# Mother_Board.net
KiCad netlist of a schematic drawn in Altium Designer
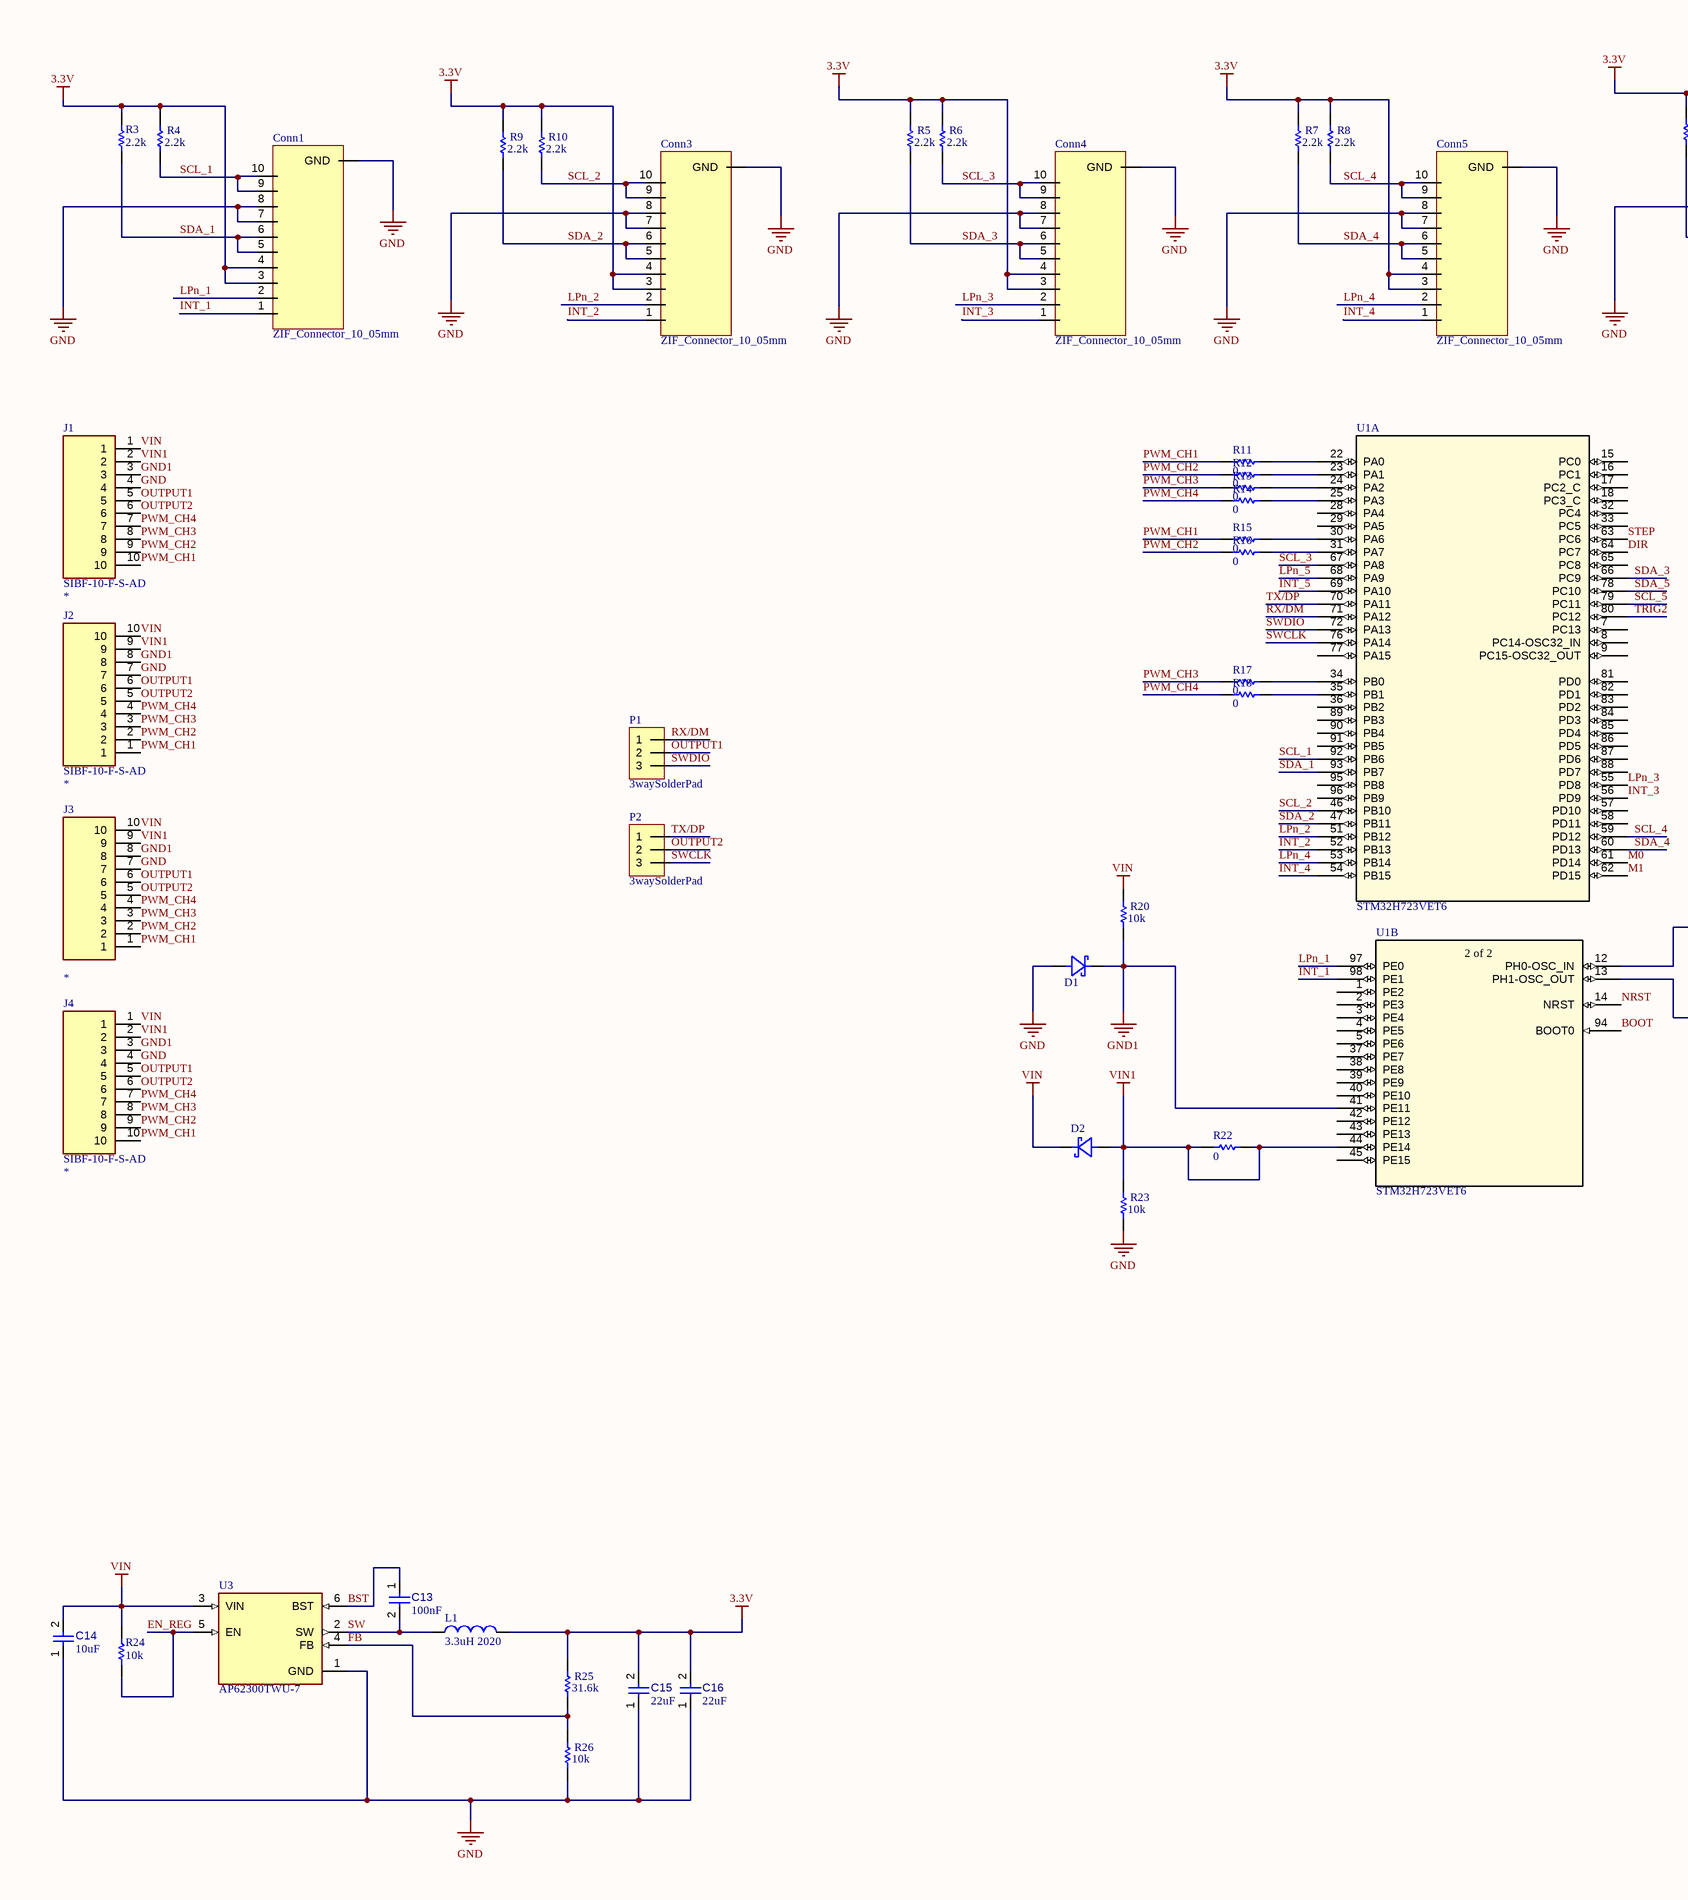
[diagram p0: Mother_Board.SchDoc, left]
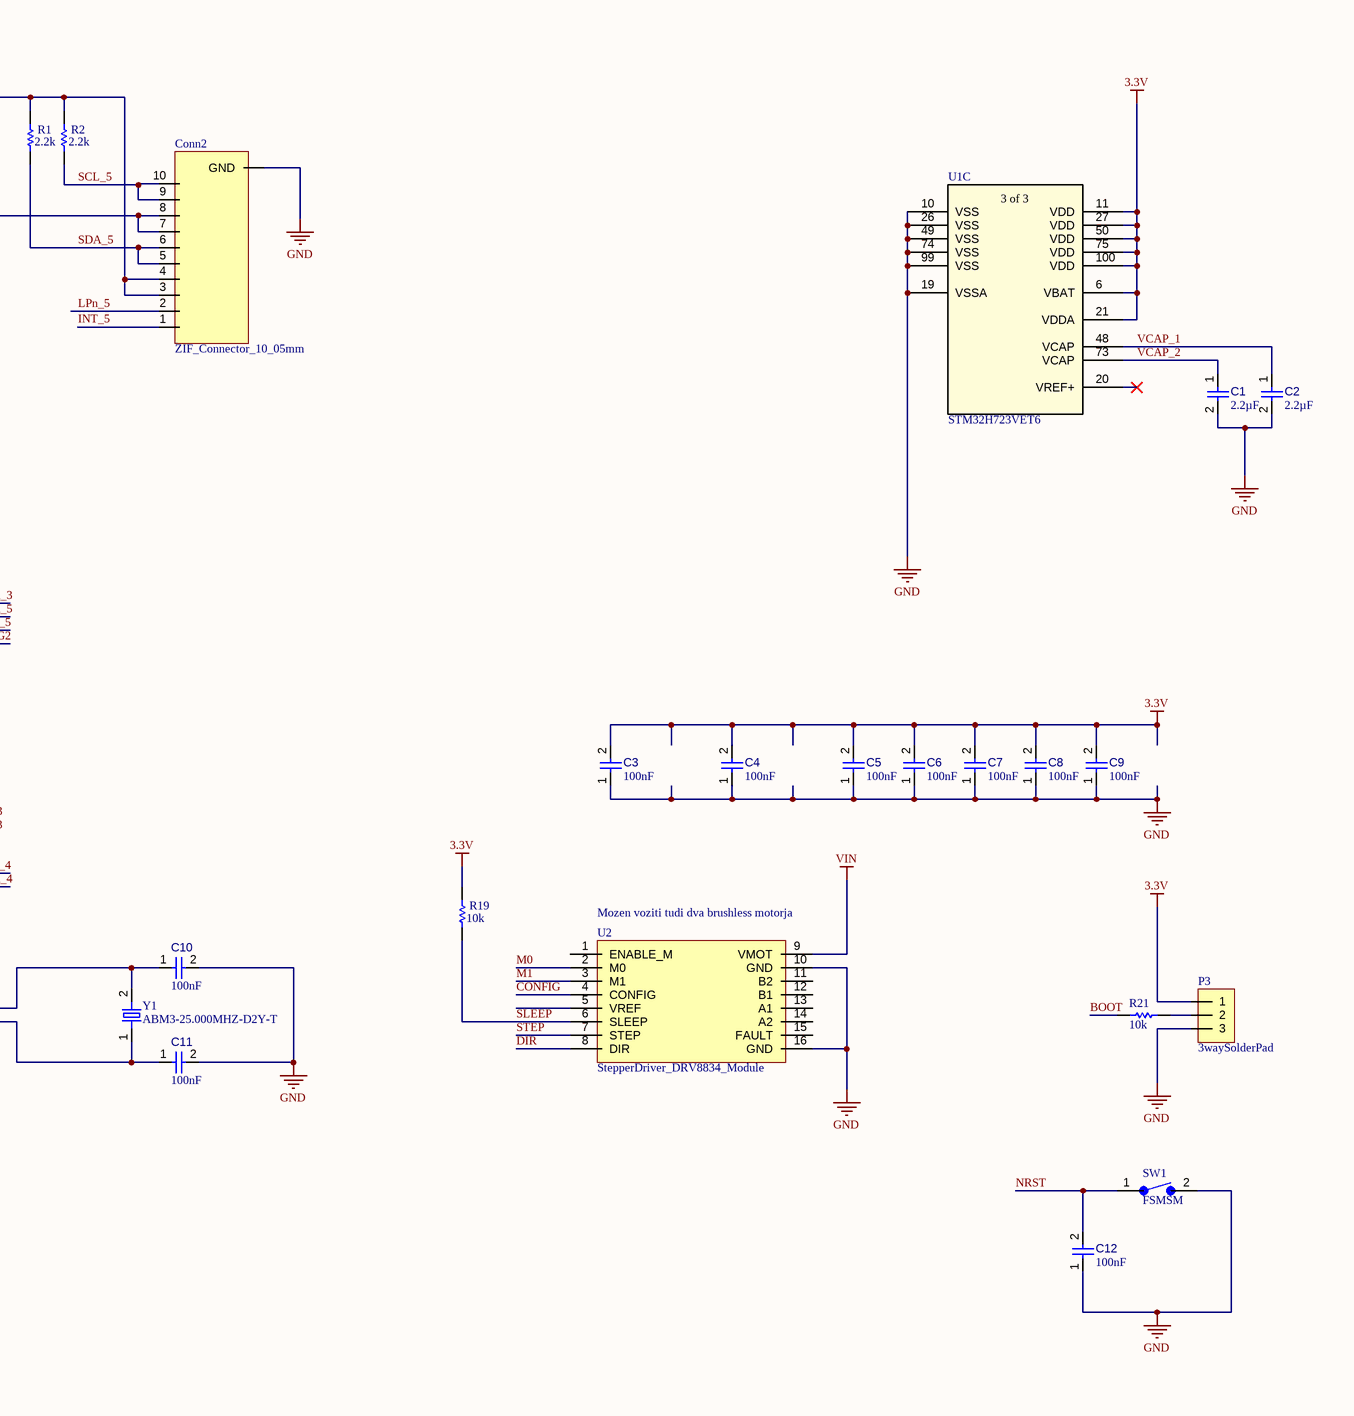
[diagram p1: Mother_Board.SchDoc, right]

(export (version "E")
  (design (tool "Eeschema 10.0.6"))
  (components
    (comp (ref "C1")
      (value "2.2µF")
      (footprint "CAPC0603(1608)100_L")
      (description "Chip Capacitor, 4.7µF +/-20%, 10V, 0603, Thickness 1 mm")
      (fields (field (name "TOLERANCE") "10%") (field (name "Comment") "Capacitor 4.7µF +/-20% 10V 0603"))
      (libsource (lib "Domen's Workpace") (part "CAP-NP-2"))
    )
    (comp (ref "C2")
      (value "2.2µF")
      (footprint "CAPC0603(1608)100_L")
      (description "Chip Capacitor, 4.7µF +/-20%, 10V, 0603, Thickness 1 mm")
      (fields (field (name "TOLERANCE") "10%") (field (name "Comment") "Capacitor 4.7µF +/-20% 10V 0603"))
      (libsource (lib "Domen's Workpace") (part "CAP-NP-2"))
    )
    (comp (ref "C3")
      (value "100nF")
      (footprint "CAPC0402(1005)60_L")
      (description "Chip Capacitor, 100nF +/-20%, 25V, 0402, Thickness 0.6 mm")
      (fields (field (name "TOLERANCE") "10%") (field (name "Comment") "Capacitor 100nF +/-20% 25V 0402"))
      (libsource (lib "Domen's Workpace") (part "CAP-NP-2"))
    )
    (comp (ref "C4")
      (value "100nF")
      (footprint "CAPC0402(1005)60_L")
      (description "Chip Capacitor, 100nF +/-20%, 25V, 0402, Thickness 0.6 mm")
      (fields (field (name "TOLERANCE") "10%") (field (name "Comment") "Capacitor 100nF +/-20% 25V 0402"))
      (libsource (lib "Domen's Workpace") (part "CAP-NP-2"))
    )
    (comp (ref "C5")
      (value "100nF")
      (footprint "CAPC0402(1005)60_L")
      (description "Chip Capacitor, 100nF +/-20%, 25V, 0402, Thickness 0.6 mm")
      (fields (field (name "TOLERANCE") "10%") (field (name "Comment") "Capacitor 100nF +/-20% 25V 0402"))
      (libsource (lib "Domen's Workpace") (part "CAP-NP-2"))
    )
    (comp (ref "C6")
      (value "100nF")
      (footprint "CAPC0402(1005)60_L")
      (description "Chip Capacitor, 100nF +/-20%, 25V, 0402, Thickness 0.6 mm")
      (fields (field (name "TOLERANCE") "10%") (field (name "Comment") "Capacitor 100nF +/-20% 25V 0402"))
      (libsource (lib "Domen's Workpace") (part "CAP-NP-2"))
    )
    (comp (ref "C7")
      (value "100nF")
      (footprint "CAPC0402(1005)60_L")
      (description "Chip Capacitor, 100nF +/-20%, 25V, 0402, Thickness 0.6 mm")
      (fields (field (name "TOLERANCE") "10%") (field (name "Comment") "Capacitor 100nF +/-20% 25V 0402"))
      (libsource (lib "Domen's Workpace") (part "CAP-NP-2"))
    )
    (comp (ref "C8")
      (value "100nF")
      (footprint "CAPC0402(1005)60_L")
      (description "Chip Capacitor, 100nF +/-20%, 25V, 0402, Thickness 0.6 mm")
      (fields (field (name "TOLERANCE") "10%") (field (name "Comment") "Capacitor 100nF +/-20% 25V 0402"))
      (libsource (lib "Domen's Workpace") (part "CAP-NP-2"))
    )
    (comp (ref "C9")
      (value "100nF")
      (footprint "CAPC0402(1005)60_L")
      (description "Chip Capacitor, 100nF +/-20%, 25V, 0402, Thickness 0.6 mm")
      (fields (field (name "TOLERANCE") "10%") (field (name "Comment") "Capacitor 100nF +/-20% 25V 0402"))
      (libsource (lib "Domen's Workpace") (part "CAP-NP-2"))
    )
    (comp (ref "C10")
      (value "100nF")
      (footprint "CAPC1608X90X40NL10T20")
      (description "Chip Capacitor, 100 nF, +/- 10%, 50 V, 0603 (1608 Metric)")
      (fields (field (name "TOLERANCE") "10%") (field (name "Comment") "Capacitor 100 nF +/-10% 50 V 0603"))
      (libsource (lib "Domen's Workpace") (part "CAP-NP-2"))
    )
    (comp (ref "C11")
      (value "100nF")
      (footprint "CAPC1608X90X40NL10T20")
      (description "Chip Capacitor, 100 nF, +/- 10%, 50 V, 0603 (1608 Metric)")
      (fields (field (name "TOLERANCE") "10%") (field (name "Comment") "Capacitor 100 nF +/-10% 50 V 0603"))
      (libsource (lib "Domen's Workpace") (part "CAP-NP-2"))
    )
    (comp (ref "C12")
      (value "100nF")
      (footprint "CAPC0402(1005)60_L")
      (description "Chip Capacitor, 100nF +/-20%, 25V, 0402, Thickness 0.6 mm")
      (fields (field (name "TOLERANCE") "10%") (field (name "Comment") "Capacitor 100nF +/-20% 25V 0402"))
      (libsource (lib "Domen's Workpace") (part "CAP-NP-2"))
    )
    (comp (ref "C13")
      (value "100nF")
      (footprint "CAPC1608X90X40NL10T20")
      (description "Chip Capacitor, 100 nF, +/- 10%, 50 V, 0603 (1608 Metric)")
      (fields (field (name "TOLERANCE") "10%") (field (name "Comment") "Capacitor 100 nF +/-10% 50 V 0603"))
      (libsource (lib "Domen's Workpace") (part "CAP-NP-2"))
    )
    (comp (ref "C14")
      (value "10uF")
      (footprint "CAPC3216X180X50NL20T25")
      (description "Chip Capacitor, 22 uF, +/- 10%, 16 V, 1206 (3216 Metric)")
      (fields (field (name "TOLERANCE") "10%") (field (name "Comment") "Capacitor 10 uF +/- 10% 16 V 1206"))
      (libsource (lib "Domen's Workpace") (part "CAP-NP-2"))
    )
    (comp (ref "C15")
      (value "22uF")
      (footprint "CAPC3216X180X50NL20T25")
      (description "Chip Capacitor, 22 uF, +/- 10%, 16 V, 1206 (3216 Metric)")
      (fields (field (name "TOLERANCE") "10%") (field (name "Comment") "Capacitor 10 uF +/- 10% 16 V 1206"))
      (libsource (lib "Domen's Workpace") (part "CAP-NP-2"))
    )
    (comp (ref "C16")
      (value "22uF")
      (footprint "CAPC3216X180X50NL20T25")
      (description "Chip Capacitor, 22 uF, +/- 10%, 16 V, 1206 (3216 Metric)")
      (fields (field (name "TOLERANCE") "10%") (field (name "Comment") "Capacitor 10 uF +/- 10% 16 V 1206"))
      (libsource (lib "Domen's Workpace") (part "CAP-NP-2"))
    )
    (comp (ref "Conn1")
      (value "ZIF_Connector_10_05mm")
      (footprint "ZIF_Connector_10_05mm")
      (libsource (lib "MainLib") (part "ZIF_Connector_10_05mm"))
    )
    (comp (ref "Conn2")
      (value "ZIF_Connector_10_05mm")
      (footprint "ZIF_Connector_10_05mm")
      (libsource (lib "MainLib") (part "ZIF_Connector_10_05mm"))
    )
    (comp (ref "Conn3")
      (value "ZIF_Connector_10_05mm")
      (footprint "ZIF_Connector_10_05mm")
      (libsource (lib "MainLib") (part "ZIF_Connector_10_05mm"))
    )
    (comp (ref "Conn4")
      (value "ZIF_Connector_10_05mm")
      (footprint "ZIF_Connector_10_05mm")
      (libsource (lib "MainLib") (part "ZIF_Connector_10_05mm"))
    )
    (comp (ref "Conn5")
      (value "ZIF_Connector_10_05mm")
      (footprint "ZIF_Connector_10_05mm")
      (libsource (lib "MainLib") (part "ZIF_Connector_10_05mm"))
    )
    (comp (ref "D1")
      (value "PMEG3030BEP,115")
      (footprint "PMEG3030BEP,115:CFP5_SOD128_NEX")
      (fields (field (name "MF") "{'manufacturer': u'Nexperia USA'}"))
      (libsource (lib "*") (part "PMEG3030BEP,115"))
    )
    (comp (ref "D2")
      (value "PMEG3030BEP,115")
      (footprint "PMEG3030BEP,115:CFP5_SOD128_NEX")
      (fields (field (name "MF") "{'manufacturer': u'Nexperia USA'}"))
      (libsource (lib "*") (part "PMEG3030BEP,115"))
    )
    (comp (ref "J1")
      (value "SIBF-10-F-S-AD")
      (footprint "SAMTEC_SIBF-10-F-S-AD")
      (fields (field (name "ALTIUM_VALUE") "*") (field (name "MF") "{'manufacturer': u'Samtec Inc.'}"))
      (libsource (lib "") (part "SIBF-10-F-S-AD_1"))
    )
    (comp (ref "J2")
      (value "SIBF-10-F-S-AD")
      (footprint "SAMTEC_SIBF-10-F-S-AD")
      (fields (field (name "ALTIUM_VALUE") "*") (field (name "MF") "{'manufacturer': u'Samtec Inc.'}"))
      (libsource (lib "SnapEDA_Library") (part "SIBF-10-F-S-AD"))
    )
    (comp (ref "J3")
      (value "~")
      (footprint "SAMTEC_SIBF-10-F-S-AD")
      (fields
        (field (name "ALTIUM_VALUE") "*")
        (field (name "MF") "{'manufacturer': u'Samtec Inc.'}")
        (field (name "MP") "SIBF-10-F-S-AD")
      )
      (libsource (lib "SnapEDA_Library") (part "SIBF-10-F-S-AD"))
    )
    (comp (ref "J4")
      (value "SIBF-10-F-S-AD")
      (footprint "SAMTEC_SIBF-10-F-S-AD")
      (fields (field (name "ALTIUM_VALUE") "*") (field (name "MF") "{'manufacturer': u'Samtec Inc.'}"))
      (libsource (lib "") (part "SIBF-10-F-S-AD_1"))
    )
    (comp (ref "L1")
      (value "3.3uH 2020")
      (footprint "IHLP2020CZER3R3M11:IHLP-2020CZ-11")
      (description "3.3ÂµH Shielded Molded Inductor 5.5A 40.4mOhm Max Nonstandard")
      (fields (field (name "MP") "IHLP2020CZER3R3M11") (field (name "MF") "{'manufacturer': u'Vishay Dale'}"))
      (libsource (lib "*") (part "IHLP2020CZER3R3M11"))
    )
    (comp (ref "P1")
      (value "3waySolderPad")
      (footprint "3waySolderPad")
      (libsource (lib "MainLib") (part "3waySolderPad"))
    )
    (comp (ref "P2")
      (value "3waySolderPad")
      (footprint "3waySolderPad")
      (libsource (lib "MainLib") (part "3waySolderPad"))
    )
    (comp (ref "P3")
      (value "3waySolderPad")
      (footprint "3waySolderPad")
      (libsource (lib "") (part "3waySolderPad_1"))
    )
    (comp (ref "R1")
      (value "2.2k")
      (footprint "RESC1608X55X25NL10T15")
      (description "Chip Resistor, 0 Ohm, 0.1 W, -55 to 155 degC, 0603 (1608 Metric)")
      (fields (field (name "POWER") "100mW") (field (name "TOLERANCE") "5%"))
      (libsource (lib "Domen's Workpace") (part "RES-2"))
    )
    (comp (ref "R2")
      (value "2.2k")
      (footprint "RESC1608X55X25NL10T15")
      (description "Chip Resistor, 0 Ohm, 0.1 W, -55 to 155 degC, 0603 (1608 Metric)")
      (fields (field (name "POWER") "100mW") (field (name "TOLERANCE") "5%"))
      (libsource (lib "Domen's Workpace") (part "RES-2"))
    )
    (comp (ref "R3")
      (value "2.2k")
      (footprint "RESC1608X55X25NL10T15")
      (description "Chip Resistor, 0 Ohm, 0.1 W, -55 to 155 degC, 0603 (1608 Metric)")
      (fields (field (name "POWER") "100mW") (field (name "TOLERANCE") "5%"))
      (libsource (lib "Domen's Workpace") (part "RES-2"))
    )
    (comp (ref "R4")
      (value "2.2k")
      (footprint "RESC1608X55X25NL10T15")
      (description "Chip Resistor, 0 Ohm, 0.1 W, -55 to 155 degC, 0603 (1608 Metric)")
      (fields (field (name "POWER") "100mW") (field (name "TOLERANCE") "5%"))
      (libsource (lib "Domen's Workpace") (part "RES-2"))
    )
    (comp (ref "R5")
      (value "2.2k")
      (footprint "RESC1608X55X25NL10T15")
      (description "Chip Resistor, 0 Ohm, 0.1 W, -55 to 155 degC, 0603 (1608 Metric)")
      (fields (field (name "POWER") "100mW") (field (name "TOLERANCE") "5%"))
      (libsource (lib "Domen's Workpace") (part "RES-2"))
    )
    (comp (ref "R6")
      (value "2.2k")
      (footprint "RESC1608X55X25NL10T15")
      (description "Chip Resistor, 0 Ohm, 0.1 W, -55 to 155 degC, 0603 (1608 Metric)")
      (fields (field (name "POWER") "100mW") (field (name "TOLERANCE") "5%"))
      (libsource (lib "Domen's Workpace") (part "RES-2"))
    )
    (comp (ref "R7")
      (value "2.2k")
      (footprint "RESC1608X55X25NL10T15")
      (description "Chip Resistor, 0 Ohm, 0.1 W, -55 to 155 degC, 0603 (1608 Metric)")
      (fields (field (name "POWER") "100mW") (field (name "TOLERANCE") "5%"))
      (libsource (lib "Domen's Workpace") (part "RES-2"))
    )
    (comp (ref "R8")
      (value "2.2k")
      (footprint "RESC1608X55X25NL10T15")
      (description "Chip Resistor, 0 Ohm, 0.1 W, -55 to 155 degC, 0603 (1608 Metric)")
      (fields (field (name "POWER") "100mW") (field (name "TOLERANCE") "5%"))
      (libsource (lib "Domen's Workpace") (part "RES-2"))
    )
    (comp (ref "R9")
      (value "2.2k")
      (footprint "RESC1608X55X25NL10T15")
      (description "Chip Resistor, 0 Ohm, 0.1 W, -55 to 155 degC, 0603 (1608 Metric)")
      (fields (field (name "POWER") "100mW") (field (name "TOLERANCE") "5%"))
      (libsource (lib "Domen's Workpace") (part "RES-2"))
    )
    (comp (ref "R10")
      (value "2.2k")
      (footprint "RESC1608X55X25NL10T15")
      (description "Chip Resistor, 0 Ohm, 0.1 W, -55 to 155 degC, 0603 (1608 Metric)")
      (fields (field (name "POWER") "100mW") (field (name "TOLERANCE") "5%"))
      (libsource (lib "Domen's Workpace") (part "RES-2"))
    )
    (comp (ref "R11")
      (value "0")
      (footprint "RESC1005X40X25ML05T05")
      (description "Chip Resistor, 0 Ohm, 0.1 W, -55 to 155 degC, 0402 (1005 Metric)")
      (fields (field (name "TOLERANCE") "5%") (field (name "POWER") "100mW"))
      (libsource (lib "Domen's Workpace") (part "RES-2"))
    )
    (comp (ref "R12")
      (value "0")
      (footprint "RESC1005X40X25ML05T05")
      (description "Chip Resistor, 0 Ohm, 0.1 W, -55 to 155 degC, 0402 (1005 Metric)")
      (fields (field (name "TOLERANCE") "5%") (field (name "POWER") "100mW"))
      (libsource (lib "Domen's Workpace") (part "RES-2"))
    )
    (comp (ref "R13")
      (value "0")
      (footprint "RESC1005X40X25ML05T05")
      (description "Chip Resistor, 0 Ohm, 0.1 W, -55 to 155 degC, 0402 (1005 Metric)")
      (fields (field (name "TOLERANCE") "5%") (field (name "POWER") "100mW"))
      (libsource (lib "Domen's Workpace") (part "RES-2"))
    )
    (comp (ref "R14")
      (value "0")
      (footprint "RESC1005X40X25ML05T05")
      (description "Chip Resistor, 0 Ohm, 0.1 W, -55 to 155 degC, 0402 (1005 Metric)")
      (fields (field (name "TOLERANCE") "5%") (field (name "POWER") "100mW"))
      (libsource (lib "Domen's Workpace") (part "RES-2"))
    )
    (comp (ref "R15")
      (value "0")
      (footprint "RESC1005X40X25ML05T05")
      (description "Chip Resistor, 0 Ohm, 0.1 W, -55 to 155 degC, 0402 (1005 Metric)")
      (fields (field (name "TOLERANCE") "5%") (field (name "POWER") "100mW"))
      (libsource (lib "Domen's Workpace") (part "RES-2"))
    )
    (comp (ref "R16")
      (value "0")
      (footprint "RESC1005X40X25ML05T05")
      (description "Chip Resistor, 0 Ohm, 0.1 W, -55 to 155 degC, 0402 (1005 Metric)")
      (fields (field (name "TOLERANCE") "5%") (field (name "POWER") "100mW"))
      (libsource (lib "Domen's Workpace") (part "RES-2"))
    )
    (comp (ref "R17")
      (value "0")
      (footprint "RESC1005X40X25ML05T05")
      (description "Chip Resistor, 0 Ohm, 0.1 W, -55 to 155 degC, 0402 (1005 Metric)")
      (fields (field (name "TOLERANCE") "5%") (field (name "POWER") "100mW"))
      (libsource (lib "Domen's Workpace") (part "RES-2"))
    )
    (comp (ref "R18")
      (value "0")
      (footprint "RESC1005X40X25ML05T05")
      (description "Chip Resistor, 0 Ohm, 0.1 W, -55 to 155 degC, 0402 (1005 Metric)")
      (fields (field (name "TOLERANCE") "5%") (field (name "POWER") "100mW"))
      (libsource (lib "Domen's Workpace") (part "RES-2"))
    )
    (comp (ref "R19")
      (value "10k")
      (footprint "RESC1608X55X25NL10T15")
      (description "Chip Resistor, 0 Ohm, 0.1 W, -55 to 155 degC, 0603 (1608 Metric)")
      (fields (field (name "POWER") "100mW") (field (name "TOLERANCE") "5%"))
      (libsource (lib "Domen's Workpace") (part "RES-2"))
    )
    (comp (ref "R20")
      (value "10k")
      (footprint "RESC1608X55X25NL10T15")
      (description "Chip Resistor, 0 Ohm, 0.1 W, -55 to 155 degC, 0603 (1608 Metric)")
      (fields (field (name "POWER") "100mW") (field (name "TOLERANCE") "5%"))
      (libsource (lib "Domen's Workpace") (part "RES-2"))
    )
    (comp (ref "R21")
      (value "10k")
      (footprint "RESC1608X55X25ML10T15")
      (description "Chip Resistor, 10 kOhm, 0.1 W, -55 to 155 degC, 0603 (1608 Metric)")
      (fields (field (name "POWER") "100mW") (field (name "TOLERANCE") "5%"))
      (libsource (lib "Domen's Workpace") (part "RES-2"))
    )
    (comp (ref "R22")
      (value "0")
      (footprint "RESC1005X40X25ML05T05")
      (description "Chip Resistor, 0 Ohm, 0.1 W, -55 to 155 degC, 0402 (1005 Metric)")
      (fields (field (name "TOLERANCE") "5%") (field (name "POWER") "100mW"))
      (libsource (lib "Domen's Workpace") (part "RES-2"))
    )
    (comp (ref "R23")
      (value "10k")
      (footprint "RESC1608X55X25NL10T15")
      (description "Chip Resistor, 0 Ohm, 0.1 W, -55 to 155 degC, 0603 (1608 Metric)")
      (fields (field (name "POWER") "100mW") (field (name "TOLERANCE") "5%"))
      (libsource (lib "Domen's Workpace") (part "RES-2"))
    )
    (comp (ref "R24")
      (value "10k")
      (footprint "RESC1608X55X25ML10T15")
      (description "Chip Resistor, 10 kOhm, 0.1 W, -55 to 155 degC, 0603 (1608 Metric)")
      (fields (field (name "POWER") "100mW") (field (name "TOLERANCE") "5%"))
      (libsource (lib "Domen's Workpace") (part "RES-2"))
    )
    (comp (ref "R25")
      (value "31.6k")
      (footprint "RESC1608X55X25NL10T15")
      (description "Chip Resistor, 0 Ohm, 0.1 W, -55 to 155 degC, 0603 (1608 Metric)")
      (fields (field (name "POWER") "100mW") (field (name "TOLERANCE") "5%"))
      (libsource (lib "Domen's Workpace") (part "RES-2"))
    )
    (comp (ref "R26")
      (value "10k")
      (footprint "RESC1608X55X25NL10T15")
      (description "Chip Resistor, 0 Ohm, 0.1 W, -55 to 155 degC, 0603 (1608 Metric)")
      (fields (field (name "POWER") "100mW") (field (name "TOLERANCE") "5%"))
      (libsource (lib "Domen's Workpace") (part "RES-2"))
    )
    (comp (ref "SW1")
      (value "FSMSM")
      (footprint "FSMSM:TE_FSMSM")
      (description "Switch Tactile OFF (ON) SPST Rectangular Button Gull Wing 0.05A 12VDC SMD Loose Piece")
      (fields (field (name "MF") "{'manufacturer': u'TE Connectivity'}"))
      (libsource (lib "*") (part "FSMSM"))
    )
    (comp (ref "U1")
      (value "STM32H723VET6")
      (footprint "LQFP100_STM")
      (description "No Description Available")
      (fields (field (name "COPYRIGHT") "Copyright (C) 2022 Ultra Librarian. All rights reserved."))
      (libsource (lib "MainLib") (part "STM32H723VET6"))
    )
    (comp (ref "U2")
      (value "StepperDriver_DRV8834_Module")
      (footprint "StepperDriver_DRV8834_Module")
      (libsource (lib "MainLib") (part "StepperDriver_DRV8834_Module"))
    )
    (comp (ref "U3")
      (value "AP62300TWU-7")
      (footprint "AP62300TWU-7:SOT95P280X100-6N")
      (fields (field (name "MF") "{'manufacturer': u'Diodes Incorporated'}"))
      (libsource (lib "*") (part "AP62300TWU-7"))
    )
    (comp (ref "Y1")
      (value "ABM3-25.000MHZ-D2Y-T")
      (footprint "XTAL500X320X130N")
      (description "Crystals 12MHz 18pF 30ppm -40C +85C")
      (fields (field (name "MF") "{'manufacturer': u'Abracon'}"))
      (libsource (lib "SnapEDA_Library") (part "ABM3-25.000MHZ-D2Y-T"))
    )
  )
  (nets
    (net (code "1") (name "/BOOT") (class "Default")
      (node (ref "R21") (pin "1") (pinfunction "1_1") (pintype "passive"))
      (node (ref "U1") (pin "94") (pinfunction "BOOT0_94") (pintype "input"))
    )
    (net (code "2") (name "/BST") (class "Default")
      (node (ref "C13") (pin "1") (pinfunction "1_1") (pintype "passive"))
      (node (ref "U3") (pin "6") (pinfunction "BST_6") (pintype "input"))
    )
    (net (code "3") (name "/CONFIG") (class "Default")
      (node (ref "U2") (pin "4") (pinfunction "CONFIG_4") (pintype "passive"))
    )
    (net (code "4") (name "/DIR") (class "Default")
      (node (ref "U1") (pin "64") (pinfunction "PC7_64") (pintype "bidirectional"))
      (node (ref "U2") (pin "8") (pinfunction "DIR_8") (pintype "passive"))
    )
    (net (code "5") (name "/EN_REG") (class "Default")
      (node (ref "R24") (pin "1") (pinfunction "1_1") (pintype "passive"))
      (node (ref "U3") (pin "5") (pinfunction "EN_5") (pintype "input"))
    )
    (net (code "6") (name "/FB") (class "Default")
      (node (ref "R25") (pin "2") (pinfunction "2_2") (pintype "passive"))
      (node (ref "R26") (pin "1") (pinfunction "1_1") (pintype "passive"))
      (node (ref "U3") (pin "4") (pinfunction "FB_4") (pintype "input"))
    )
    (net (code "7") (name "/INT_1") (class "Default")
      (node (ref "Conn1") (pin "1") (pinfunction "1_1") (pintype "passive"))
      (node (ref "U1") (pin "98") (pinfunction "PE1_98") (pintype "bidirectional"))
    )
    (net (code "8") (name "/INT_2") (class "Default")
      (node (ref "Conn3") (pin "1") (pinfunction "1_1") (pintype "passive"))
      (node (ref "U1") (pin "52") (pinfunction "PB13_52") (pintype "bidirectional"))
    )
    (net (code "9") (name "/INT_3") (class "Default")
      (node (ref "Conn4") (pin "1") (pinfunction "1_1") (pintype "passive"))
      (node (ref "U1") (pin "56") (pinfunction "PD9_56") (pintype "bidirectional"))
    )
    (net (code "10") (name "/INT_4") (class "Default")
      (node (ref "Conn5") (pin "1") (pinfunction "1_1") (pintype "passive"))
      (node (ref "U1") (pin "54") (pinfunction "PB15_54") (pintype "bidirectional"))
    )
    (net (code "11") (name "/INT_5") (class "Default")
      (node (ref "Conn2") (pin "1") (pinfunction "1_1") (pintype "passive"))
      (node (ref "U1") (pin "69") (pinfunction "PA10_69") (pintype "bidirectional"))
    )
    (net (code "12") (name "/LPn_1") (class "Default")
      (node (ref "Conn1") (pin "2") (pinfunction "2_2") (pintype "passive"))
      (node (ref "U1") (pin "97") (pinfunction "PE0_97") (pintype "bidirectional"))
    )
    (net (code "13") (name "/LPn_2") (class "Default")
      (node (ref "Conn3") (pin "2") (pinfunction "2_2") (pintype "passive"))
      (node (ref "U1") (pin "51") (pinfunction "PB12_51") (pintype "bidirectional"))
    )
    (net (code "14") (name "/LPn_3") (class "Default")
      (node (ref "Conn4") (pin "2") (pinfunction "2_2") (pintype "passive"))
      (node (ref "U1") (pin "55") (pinfunction "PD8_55") (pintype "bidirectional"))
    )
    (net (code "15") (name "/LPn_4") (class "Default")
      (node (ref "Conn5") (pin "2") (pinfunction "2_2") (pintype "passive"))
      (node (ref "U1") (pin "53") (pinfunction "PB14_53") (pintype "bidirectional"))
    )
    (net (code "16") (name "/LPn_5") (class "Default")
      (node (ref "Conn2") (pin "2") (pinfunction "2_2") (pintype "passive"))
      (node (ref "U1") (pin "68") (pinfunction "PA9_68") (pintype "bidirectional"))
    )
    (net (code "17") (name "/M0") (class "Default")
      (node (ref "U1") (pin "61") (pinfunction "PD14_61") (pintype "bidirectional"))
      (node (ref "U2") (pin "2") (pinfunction "M0_2") (pintype "passive"))
    )
    (net (code "18") (name "/M1") (class "Default")
      (node (ref "U1") (pin "62") (pinfunction "PD15_62") (pintype "bidirectional"))
      (node (ref "U2") (pin "3") (pinfunction "M1_3") (pintype "passive"))
    )
    (net (code "19") (name "/NRST") (class "Default")
      (node (ref "C12") (pin "2") (pinfunction "2_2") (pintype "passive"))
      (node (ref "SW1") (pin "1") (pinfunction "1_1") (pintype "passive"))
      (node (ref "U1") (pin "14") (pinfunction "NRST_14") (pintype "bidirectional"))
    )
    (net (code "20") (name "/OUTPUT1") (class "Default")
      (node (ref "J1") (pin "5") (pinfunction "5_5") (pintype "passive"))
      (node (ref "J2") (pin "6") (pinfunction "6_6") (pintype "passive"))
      (node (ref "J3") (pin "6") (pinfunction "6_6") (pintype "passive"))
      (node (ref "J4") (pin "5") (pinfunction "5_5") (pintype "passive"))
      (node (ref "P1") (pin "2") (pinfunction "2_2") (pintype "passive"))
    )
    (net (code "21") (name "/OUTPUT2") (class "Default")
      (node (ref "J1") (pin "6") (pinfunction "6_6") (pintype "passive"))
      (node (ref "J2") (pin "5") (pinfunction "5_5") (pintype "passive"))
      (node (ref "J3") (pin "5") (pinfunction "5_5") (pintype "passive"))
      (node (ref "J4") (pin "6") (pinfunction "6_6") (pintype "passive"))
      (node (ref "P2") (pin "2") (pinfunction "2_2") (pintype "passive"))
    )
    (net (code "22") (name "/PWM_CH1") (class "Default")
      (node (ref "J1") (pin "10") (pinfunction "10_10") (pintype "passive"))
      (node (ref "J2") (pin "1") (pinfunction "1_1") (pintype "passive"))
      (node (ref "J3") (pin "1") (pinfunction "1_1") (pintype "passive"))
      (node (ref "J4") (pin "10") (pinfunction "10_10") (pintype "passive"))
      (node (ref "R11") (pin "1") (pinfunction "1_1") (pintype "passive"))
      (node (ref "R15") (pin "1") (pinfunction "1_1") (pintype "passive"))
    )
    (net (code "23") (name "/PWM_CH2") (class "Default")
      (node (ref "J1") (pin "9") (pinfunction "9_9") (pintype "passive"))
      (node (ref "J2") (pin "2") (pinfunction "2_2") (pintype "passive"))
      (node (ref "J3") (pin "2") (pinfunction "2_2") (pintype "passive"))
      (node (ref "J4") (pin "9") (pinfunction "9_9") (pintype "passive"))
      (node (ref "R12") (pin "1") (pinfunction "1_1") (pintype "passive"))
      (node (ref "R16") (pin "1") (pinfunction "1_1") (pintype "passive"))
    )
    (net (code "24") (name "/PWM_CH3") (class "Default")
      (node (ref "J1") (pin "8") (pinfunction "8_8") (pintype "passive"))
      (node (ref "J2") (pin "3") (pinfunction "3_3") (pintype "passive"))
      (node (ref "J3") (pin "3") (pinfunction "3_3") (pintype "passive"))
      (node (ref "J4") (pin "8") (pinfunction "8_8") (pintype "passive"))
      (node (ref "R13") (pin "1") (pinfunction "1_1") (pintype "passive"))
      (node (ref "R17") (pin "1") (pinfunction "1_1") (pintype "passive"))
    )
    (net (code "25") (name "/PWM_CH4") (class "Default")
      (node (ref "J1") (pin "7") (pinfunction "7_7") (pintype "passive"))
      (node (ref "J2") (pin "4") (pinfunction "4_4") (pintype "passive"))
      (node (ref "J3") (pin "4") (pinfunction "4_4") (pintype "passive"))
      (node (ref "J4") (pin "7") (pinfunction "7_7") (pintype "passive"))
      (node (ref "R14") (pin "1") (pinfunction "1_1") (pintype "passive"))
      (node (ref "R18") (pin "1") (pinfunction "1_1") (pintype "passive"))
    )
    (net (code "26") (name "/RX{slash}DM") (class "Default")
      (node (ref "P1") (pin "1") (pinfunction "1_1") (pintype "passive"))
      (node (ref "U1") (pin "71") (pinfunction "PA12_71") (pintype "bidirectional"))
    )
    (net (code "27") (name "/SCL_1") (class "Default")
      (node (ref "Conn1") (pin "10") (pinfunction "10_10") (pintype "passive"))
      (node (ref "Conn1") (pin "9") (pinfunction "9_9") (pintype "passive"))
      (node (ref "R4") (pin "2") (pinfunction "2_2") (pintype "passive"))
      (node (ref "U1") (pin "92") (pinfunction "PB6_92") (pintype "bidirectional"))
    )
    (net (code "28") (name "/SCL_2") (class "Default")
      (node (ref "Conn3") (pin "10") (pinfunction "10_10") (pintype "passive"))
      (node (ref "Conn3") (pin "9") (pinfunction "9_9") (pintype "passive"))
      (node (ref "R10") (pin "2") (pinfunction "2_2") (pintype "passive"))
      (node (ref "U1") (pin "46") (pinfunction "PB10_46") (pintype "bidirectional"))
    )
    (net (code "29") (name "/SCL_3") (class "Default")
      (node (ref "Conn4") (pin "10") (pinfunction "10_10") (pintype "passive"))
      (node (ref "Conn4") (pin "9") (pinfunction "9_9") (pintype "passive"))
      (node (ref "R6") (pin "2") (pinfunction "2_2") (pintype "passive"))
      (node (ref "U1") (pin "67") (pinfunction "PA8_67") (pintype "bidirectional"))
    )
    (net (code "30") (name "/SCL_4") (class "Default")
      (node (ref "Conn5") (pin "10") (pinfunction "10_10") (pintype "passive"))
      (node (ref "Conn5") (pin "9") (pinfunction "9_9") (pintype "passive"))
      (node (ref "R8") (pin "2") (pinfunction "2_2") (pintype "passive"))
      (node (ref "U1") (pin "59") (pinfunction "PD12_59") (pintype "bidirectional"))
    )
    (net (code "31") (name "/SCL_5") (class "Default")
      (node (ref "Conn2") (pin "10") (pinfunction "10_10") (pintype "passive"))
      (node (ref "Conn2") (pin "9") (pinfunction "9_9") (pintype "passive"))
      (node (ref "R2") (pin "2") (pinfunction "2_2") (pintype "passive"))
      (node (ref "U1") (pin "79") (pinfunction "PC11_79") (pintype "bidirectional"))
    )
    (net (code "32") (name "/SDA_1") (class "Default")
      (node (ref "Conn1") (pin "5") (pinfunction "5_5") (pintype "passive"))
      (node (ref "Conn1") (pin "6") (pinfunction "6_6") (pintype "passive"))
      (node (ref "R3") (pin "2") (pinfunction "2_2") (pintype "passive"))
      (node (ref "U1") (pin "93") (pinfunction "PB7_93") (pintype "bidirectional"))
    )
    (net (code "33") (name "/SDA_2") (class "Default")
      (node (ref "Conn3") (pin "5") (pinfunction "5_5") (pintype "passive"))
      (node (ref "Conn3") (pin "6") (pinfunction "6_6") (pintype "passive"))
      (node (ref "R9") (pin "2") (pinfunction "2_2") (pintype "passive"))
      (node (ref "U1") (pin "47") (pinfunction "PB11_47") (pintype "bidirectional"))
    )
    (net (code "34") (name "/SDA_3") (class "Default")
      (node (ref "Conn4") (pin "5") (pinfunction "5_5") (pintype "passive"))
      (node (ref "Conn4") (pin "6") (pinfunction "6_6") (pintype "passive"))
      (node (ref "R5") (pin "2") (pinfunction "2_2") (pintype "passive"))
      (node (ref "U1") (pin "66") (pinfunction "PC9_66") (pintype "bidirectional"))
    )
    (net (code "35") (name "/SDA_4") (class "Default")
      (node (ref "Conn5") (pin "5") (pinfunction "5_5") (pintype "passive"))
      (node (ref "Conn5") (pin "6") (pinfunction "6_6") (pintype "passive"))
      (node (ref "R7") (pin "2") (pinfunction "2_2") (pintype "passive"))
      (node (ref "U1") (pin "60") (pinfunction "PD13_60") (pintype "bidirectional"))
    )
    (net (code "36") (name "/SDA_5") (class "Default")
      (node (ref "Conn2") (pin "5") (pinfunction "5_5") (pintype "passive"))
      (node (ref "Conn2") (pin "6") (pinfunction "6_6") (pintype "passive"))
      (node (ref "R1") (pin "2") (pinfunction "2_2") (pintype "passive"))
      (node (ref "U1") (pin "78") (pinfunction "PC10_78") (pintype "bidirectional"))
    )
    (net (code "37") (name "/SLEEP") (class "Default")
      (node (ref "R19") (pin "2") (pinfunction "2_2") (pintype "passive"))
      (node (ref "U2") (pin "6") (pinfunction "SLEEP_6") (pintype "passive"))
    )
    (net (code "38") (name "/STEP") (class "Default")
      (node (ref "U1") (pin "63") (pinfunction "PC6_63") (pintype "bidirectional"))
      (node (ref "U2") (pin "7") (pinfunction "STEP_7") (pintype "passive"))
    )
    (net (code "39") (name "/SW") (class "Default")
      (node (ref "C13") (pin "2") (pinfunction "2_2") (pintype "passive"))
      (node (ref "L1") (pin "P$1") (pinfunction "P$1_P$1") (pintype "bidirectional"))
      (node (ref "U3") (pin "2") (pinfunction "SW_2") (pintype "output"))
    )
    (net (code "40") (name "/SWCLK") (class "Default")
      (node (ref "P2") (pin "3") (pinfunction "3_3") (pintype "passive"))
      (node (ref "U1") (pin "76") (pinfunction "PA14_76") (pintype "bidirectional"))
    )
    (net (code "41") (name "/SWDIO") (class "Default")
      (node (ref "P1") (pin "3") (pinfunction "3_3") (pintype "passive"))
      (node (ref "U1") (pin "72") (pinfunction "PA13_72") (pintype "bidirectional"))
    )
    (net (code "42") (name "/TRIG2") (class "Default")
      (node (ref "U1") (pin "80") (pinfunction "PC12_80") (pintype "bidirectional"))
    )
    (net (code "43") (name "/TX{slash}DP") (class "Default")
      (node (ref "P2") (pin "1") (pinfunction "1_1") (pintype "passive"))
      (node (ref "U1") (pin "70") (pinfunction "PA11_70") (pintype "bidirectional"))
    )
    (net (code "44") (name "/VCAP_1") (class "Default")
      (node (ref "C2") (pin "1") (pinfunction "1_1") (pintype "passive"))
      (node (ref "U1") (pin "48") (pinfunction "VCAP_48") (pintype "power_in"))
    )
    (net (code "45") (name "/VCAP_2") (class "Default")
      (node (ref "C1") (pin "1") (pinfunction "1_1") (pintype "passive"))
      (node (ref "U1") (pin "73") (pinfunction "VCAP_73") (pintype "power_in"))
    )
    (net (code "46") (name "3.3V") (class "Default")
      (node (ref "C15") (pin "2") (pinfunction "2_2") (pintype "passive"))
      (node (ref "C16") (pin "2") (pinfunction "2_2") (pintype "passive"))
      (node (ref "C3") (pin "2") (pinfunction "2_2") (pintype "passive"))
      (node (ref "C4") (pin "2") (pinfunction "2_2") (pintype "passive"))
      (node (ref "C5") (pin "2") (pinfunction "2_2") (pintype "passive"))
      (node (ref "C6") (pin "2") (pinfunction "2_2") (pintype "passive"))
      (node (ref "C7") (pin "2") (pinfunction "2_2") (pintype "passive"))
      (node (ref "C8") (pin "2") (pinfunction "2_2") (pintype "passive"))
      (node (ref "C9") (pin "2") (pinfunction "2_2") (pintype "passive"))
      (node (ref "Conn1") (pin "3") (pinfunction "3_3") (pintype "passive"))
      (node (ref "Conn1") (pin "4") (pinfunction "4_4") (pintype "passive"))
      (node (ref "Conn2") (pin "3") (pinfunction "3_3") (pintype "passive"))
      (node (ref "Conn2") (pin "4") (pinfunction "4_4") (pintype "passive"))
      (node (ref "Conn3") (pin "3") (pinfunction "3_3") (pintype "passive"))
      (node (ref "Conn3") (pin "4") (pinfunction "4_4") (pintype "passive"))
      (node (ref "Conn4") (pin "3") (pinfunction "3_3") (pintype "passive"))
      (node (ref "Conn4") (pin "4") (pinfunction "4_4") (pintype "passive"))
      (node (ref "Conn5") (pin "3") (pinfunction "3_3") (pintype "passive"))
      (node (ref "Conn5") (pin "4") (pinfunction "4_4") (pintype "passive"))
      (node (ref "L1") (pin "P$2") (pinfunction "P$2_P$2") (pintype "bidirectional"))
      (node (ref "P3") (pin "1") (pinfunction "1_1") (pintype "passive"))
      (node (ref "R1") (pin "1") (pinfunction "1_1") (pintype "passive"))
      (node (ref "R10") (pin "1") (pinfunction "1_1") (pintype "passive"))
      (node (ref "R19") (pin "1") (pinfunction "1_1") (pintype "passive"))
      (node (ref "R2") (pin "1") (pinfunction "1_1") (pintype "passive"))
      (node (ref "R25") (pin "1") (pinfunction "1_1") (pintype "passive"))
      (node (ref "R3") (pin "1") (pinfunction "1_1") (pintype "passive"))
      (node (ref "R4") (pin "1") (pinfunction "1_1") (pintype "passive"))
      (node (ref "R5") (pin "1") (pinfunction "1_1") (pintype "passive"))
      (node (ref "R6") (pin "1") (pinfunction "1_1") (pintype "passive"))
      (node (ref "R7") (pin "1") (pinfunction "1_1") (pintype "passive"))
      (node (ref "R8") (pin "1") (pinfunction "1_1") (pintype "passive"))
      (node (ref "R9") (pin "1") (pinfunction "1_1") (pintype "passive"))
      (node (ref "U1") (pin "100") (pinfunction "VDD_100") (pintype "power_in"))
      (node (ref "U1") (pin "11") (pinfunction "VDD_11") (pintype "power_in"))
      (node (ref "U1") (pin "21") (pinfunction "VDDA_21") (pintype "power_in"))
      (node (ref "U1") (pin "27") (pinfunction "VDD_27") (pintype "power_in"))
      (node (ref "U1") (pin "50") (pinfunction "VDD_50") (pintype "power_in"))
      (node (ref "U1") (pin "6") (pinfunction "VBAT_6") (pintype "power_in"))
      (node (ref "U1") (pin "75") (pinfunction "VDD_75") (pintype "power_in"))
    )
    (net (code "47") (name "GND") (class "Default")
      (node (ref "C1") (pin "2") (pinfunction "2_2") (pintype "passive"))
      (node (ref "C10") (pin "2") (pinfunction "2_2") (pintype "passive"))
      (node (ref "C11") (pin "2") (pinfunction "2_2") (pintype "passive"))
      (node (ref "C12") (pin "1") (pinfunction "1_1") (pintype "passive"))
      (node (ref "C14") (pin "1") (pinfunction "1_1") (pintype "passive"))
      (node (ref "C15") (pin "1") (pinfunction "1_1") (pintype "passive"))
      (node (ref "C16") (pin "1") (pinfunction "1_1") (pintype "passive"))
      (node (ref "C2") (pin "2") (pinfunction "2_2") (pintype "passive"))
      (node (ref "C3") (pin "1") (pinfunction "1_1") (pintype "passive"))
      (node (ref "C4") (pin "1") (pinfunction "1_1") (pintype "passive"))
      (node (ref "C5") (pin "1") (pinfunction "1_1") (pintype "passive"))
      (node (ref "C6") (pin "1") (pinfunction "1_1") (pintype "passive"))
      (node (ref "C7") (pin "1") (pinfunction "1_1") (pintype "passive"))
      (node (ref "C8") (pin "1") (pinfunction "1_1") (pintype "passive"))
      (node (ref "C9") (pin "1") (pinfunction "1_1") (pintype "passive"))
      (node (ref "Conn1") (pin "7") (pinfunction "7_7") (pintype "passive"))
      (node (ref "Conn1") (pin "8") (pinfunction "8_8") (pintype "passive"))
      (node (ref "Conn1") (pin "GND") (pinfunction "GND_GND") (pintype "passive"))
      (node (ref "Conn2") (pin "7") (pinfunction "7_7") (pintype "passive"))
      (node (ref "Conn2") (pin "8") (pinfunction "8_8") (pintype "passive"))
      (node (ref "Conn2") (pin "GND") (pinfunction "GND_GND") (pintype "passive"))
      (node (ref "Conn3") (pin "7") (pinfunction "7_7") (pintype "passive"))
      (node (ref "Conn3") (pin "8") (pinfunction "8_8") (pintype "passive"))
      (node (ref "Conn3") (pin "GND") (pinfunction "GND_GND") (pintype "passive"))
      (node (ref "Conn4") (pin "7") (pinfunction "7_7") (pintype "passive"))
      (node (ref "Conn4") (pin "8") (pinfunction "8_8") (pintype "passive"))
      (node (ref "Conn4") (pin "GND") (pinfunction "GND_GND") (pintype "passive"))
      (node (ref "Conn5") (pin "7") (pinfunction "7_7") (pintype "passive"))
      (node (ref "Conn5") (pin "8") (pinfunction "8_8") (pintype "passive"))
      (node (ref "Conn5") (pin "GND") (pinfunction "GND_GND") (pintype "passive"))
      (node (ref "D1") (pin "2") (pinfunction "12_2") (pintype "passive"))
      (node (ref "J1") (pin "4") (pinfunction "4_4") (pintype "passive"))
      (node (ref "J2") (pin "7") (pinfunction "7_7") (pintype "passive"))
      (node (ref "J3") (pin "7") (pinfunction "7_7") (pintype "passive"))
      (node (ref "J4") (pin "4") (pinfunction "4_4") (pintype "passive"))
      (node (ref "P3") (pin "3") (pinfunction "3_3") (pintype "passive"))
      (node (ref "R23") (pin "2") (pinfunction "2_2") (pintype "passive"))
      (node (ref "R26") (pin "2") (pinfunction "2_2") (pintype "passive"))
      (node (ref "SW1") (pin "2") (pinfunction "2_2") (pintype "passive"))
      (node (ref "U1") (pin "10") (pinfunction "VSS_10") (pintype "power_in"))
      (node (ref "U1") (pin "19") (pinfunction "VSSA_19") (pintype "power_in"))
      (node (ref "U1") (pin "26") (pinfunction "VSS_26") (pintype "power_in"))
      (node (ref "U1") (pin "49") (pinfunction "VSS_49") (pintype "power_in"))
      (node (ref "U1") (pin "74") (pinfunction "VSS_74") (pintype "power_in"))
      (node (ref "U1") (pin "99") (pinfunction "VSS_99") (pintype "power_in"))
      (node (ref "U2") (pin "10") (pinfunction "GND_10") (pintype "passive"))
      (node (ref "U2") (pin "16") (pinfunction "GND_16") (pintype "passive"))
      (node (ref "U3") (pin "1") (pinfunction "GND_1") (pintype "power_in"))
    )
    (net (code "48") (name "GND1") (class "Default")
      (node (ref "D1") (pin "1") (pinfunction "11_1") (pintype "passive"))
      (node (ref "J1") (pin "3") (pinfunction "3_3") (pintype "passive"))
      (node (ref "J2") (pin "8") (pinfunction "8_8") (pintype "passive"))
      (node (ref "J3") (pin "8") (pinfunction "8_8") (pintype "passive"))
      (node (ref "J4") (pin "3") (pinfunction "3_3") (pintype "passive"))
      (node (ref "R20") (pin "2") (pinfunction "2_2") (pintype "passive"))
      (node (ref "U1") (pin "41") (pinfunction "PE11_41") (pintype "bidirectional"))
    )
    (net (code "49") (name "Net-(P3-Pad2)") (class "Default")
      (node (ref "P3") (pin "2") (pinfunction "2_2") (pintype "passive"))
      (node (ref "R21") (pin "2") (pinfunction "2_2") (pintype "passive"))
    )
    (net (code "50") (name "Net-(U1A-PA0)") (class "Default")
      (node (ref "R11") (pin "2") (pinfunction "2_2") (pintype "passive"))
      (node (ref "U1") (pin "22") (pinfunction "PA0_22") (pintype "bidirectional"))
    )
    (net (code "51") (name "Net-(U1A-PA1)") (class "Default")
      (node (ref "R12") (pin "2") (pinfunction "2_2") (pintype "passive"))
      (node (ref "U1") (pin "23") (pinfunction "PA1_23") (pintype "bidirectional"))
    )
    (net (code "52") (name "Net-(U1A-PA2)") (class "Default")
      (node (ref "R13") (pin "2") (pinfunction "2_2") (pintype "passive"))
      (node (ref "U1") (pin "24") (pinfunction "PA2_24") (pintype "bidirectional"))
    )
    (net (code "53") (name "Net-(U1A-PA3)") (class "Default")
      (node (ref "R14") (pin "2") (pinfunction "2_2") (pintype "passive"))
      (node (ref "U1") (pin "25") (pinfunction "PA3_25") (pintype "bidirectional"))
    )
    (net (code "54") (name "Net-(U1A-PA6)") (class "Default")
      (node (ref "R15") (pin "2") (pinfunction "2_2") (pintype "passive"))
      (node (ref "U1") (pin "30") (pinfunction "PA6_30") (pintype "bidirectional"))
    )
    (net (code "55") (name "Net-(U1A-PA7)") (class "Default")
      (node (ref "R16") (pin "2") (pinfunction "2_2") (pintype "passive"))
      (node (ref "U1") (pin "31") (pinfunction "PA7_31") (pintype "bidirectional"))
    )
    (net (code "56") (name "Net-(U1A-PB0)") (class "Default")
      (node (ref "R17") (pin "2") (pinfunction "2_2") (pintype "passive"))
      (node (ref "U1") (pin "34") (pinfunction "PB0_34") (pintype "bidirectional"))
    )
    (net (code "57") (name "Net-(U1A-PB1)") (class "Default")
      (node (ref "R18") (pin "2") (pinfunction "2_2") (pintype "passive"))
      (node (ref "U1") (pin "35") (pinfunction "PB1_35") (pintype "bidirectional"))
    )
    (net (code "58") (name "Net-(U1B-PH0-OSC_IN)") (class "Default")
      (node (ref "C10") (pin "1") (pinfunction "1_1") (pintype "passive"))
      (node (ref "U1") (pin "12") (pinfunction "PH0-OSC_IN_12") (pintype "bidirectional"))
      (node (ref "Y1") (pin "2") (pinfunction "2_2") (pintype "passive"))
    )
    (net (code "59") (name "Net-(U1B-PH1-OSC_OUT)") (class "Default")
      (node (ref "C11") (pin "1") (pinfunction "1_1") (pintype "passive"))
      (node (ref "U1") (pin "13") (pinfunction "PH1-OSC_OUT_13") (pintype "bidirectional"))
      (node (ref "Y1") (pin "1") (pinfunction "1_1") (pintype "passive"))
    )
    (net (code "60") (name "VIN") (class "Default")
      (node (ref "C14") (pin "2") (pinfunction "2_2") (pintype "passive"))
      (node (ref "D2") (pin "1") (pinfunction "11_1") (pintype "passive"))
      (node (ref "J1") (pin "1") (pinfunction "1_1") (pintype "passive"))
      (node (ref "J2") (pin "10") (pinfunction "10_10") (pintype "passive"))
      (node (ref "J3") (pin "10") (pinfunction "10_10") (pintype "passive"))
      (node (ref "J4") (pin "1") (pinfunction "1_1") (pintype "passive"))
      (node (ref "R20") (pin "1") (pinfunction "1_1") (pintype "passive"))
      (node (ref "R24") (pin "2") (pinfunction "2_2") (pintype "passive"))
      (node (ref "U2") (pin "9") (pinfunction "VMOT_9") (pintype "passive"))
      (node (ref "U3") (pin "3") (pinfunction "VIN_3") (pintype "input"))
    )
    (net (code "61") (name "VIN1") (class "Default")
      (node (ref "D2") (pin "2") (pinfunction "12_2") (pintype "passive"))
      (node (ref "J1") (pin "2") (pinfunction "2_2") (pintype "passive"))
      (node (ref "J2") (pin "9") (pinfunction "9_9") (pintype "passive"))
      (node (ref "J3") (pin "9") (pinfunction "9_9") (pintype "passive"))
      (node (ref "J4") (pin "2") (pinfunction "2_2") (pintype "passive"))
      (node (ref "R22") (pin "1") (pinfunction "1_1") (pintype "passive"))
      (node (ref "R22") (pin "2") (pinfunction "2_2") (pintype "passive"))
      (node (ref "R23") (pin "1") (pinfunction "1_1") (pintype "passive"))
      (node (ref "U1") (pin "44") (pinfunction "PE14_44") (pintype "bidirectional"))
    )
    (net (code "62") (name "unconnected-(U1A-PA4-Pad28)") (class "Default")
      (node (ref "U1") (pin "28") (pinfunction "PA4_28") (pintype "bidirectional"))
    )
    (net (code "63") (name "unconnected-(U1A-PA5-Pad29)") (class "Default")
      (node (ref "U1") (pin "29") (pinfunction "PA5_29") (pintype "bidirectional"))
    )
    (net (code "64") (name "unconnected-(U1A-PA15-Pad77)") (class "Default")
      (node (ref "U1") (pin "77") (pinfunction "PA15_77") (pintype "bidirectional"))
    )
    (net (code "65") (name "unconnected-(U1A-PB2-Pad36)") (class "Default")
      (node (ref "U1") (pin "36") (pinfunction "PB2_36") (pintype "bidirectional"))
    )
    (net (code "66") (name "unconnected-(U1A-PB3-Pad89)") (class "Default")
      (node (ref "U1") (pin "89") (pinfunction "PB3_89") (pintype "bidirectional"))
    )
    (net (code "67") (name "unconnected-(U1A-PB4-Pad90)") (class "Default")
      (node (ref "U1") (pin "90") (pinfunction "PB4_90") (pintype "bidirectional"))
    )
    (net (code "68") (name "unconnected-(U1A-PB5-Pad91)") (class "Default")
      (node (ref "U1") (pin "91") (pinfunction "PB5_91") (pintype "bidirectional"))
    )
    (net (code "69") (name "unconnected-(U1A-PB8-Pad95)") (class "Default")
      (node (ref "U1") (pin "95") (pinfunction "PB8_95") (pintype "bidirectional"))
    )
    (net (code "70") (name "unconnected-(U1A-PB9-Pad96)") (class "Default")
      (node (ref "U1") (pin "96") (pinfunction "PB9_96") (pintype "bidirectional"))
    )
    (net (code "71") (name "unconnected-(U1A-PC0-Pad15)") (class "Default")
      (node (ref "U1") (pin "15") (pinfunction "PC0_15") (pintype "bidirectional"))
    )
    (net (code "72") (name "unconnected-(U1A-PC1-Pad16)") (class "Default")
      (node (ref "U1") (pin "16") (pinfunction "PC1_16") (pintype "bidirectional"))
    )
    (net (code "73") (name "unconnected-(U1A-PC2_C-Pad17)") (class "Default")
      (node (ref "U1") (pin "17") (pinfunction "PC2_C_17") (pintype "bidirectional"))
    )
    (net (code "74") (name "unconnected-(U1A-PC3_C-Pad18)") (class "Default")
      (node (ref "U1") (pin "18") (pinfunction "PC3_C_18") (pintype "bidirectional"))
    )
    (net (code "75") (name "unconnected-(U1A-PC4-Pad32)") (class "Default")
      (node (ref "U1") (pin "32") (pinfunction "PC4_32") (pintype "bidirectional"))
    )
    (net (code "76") (name "unconnected-(U1A-PC5-Pad33)") (class "Default")
      (node (ref "U1") (pin "33") (pinfunction "PC5_33") (pintype "bidirectional"))
    )
    (net (code "77") (name "unconnected-(U1A-PC8-Pad65)") (class "Default")
      (node (ref "U1") (pin "65") (pinfunction "PC8_65") (pintype "bidirectional"))
    )
    (net (code "78") (name "unconnected-(U1A-PC13-Pad7)") (class "Default")
      (node (ref "U1") (pin "7") (pinfunction "PC13_7") (pintype "bidirectional"))
    )
    (net (code "79") (name "unconnected-(U1A-PC14-OSC32_IN-Pad8)") (class "Default")
      (node (ref "U1") (pin "8") (pinfunction "PC14-OSC32_IN_8") (pintype "bidirectional"))
    )
    (net (code "80") (name "unconnected-(U1A-PC15-OSC32_OUT-Pad9)") (class "Default")
      (node (ref "U1") (pin "9") (pinfunction "PC15-OSC32_OUT_9") (pintype "bidirectional"))
    )
    (net (code "81") (name "unconnected-(U1A-PD0-Pad81)") (class "Default")
      (node (ref "U1") (pin "81") (pinfunction "PD0_81") (pintype "bidirectional"))
    )
    (net (code "82") (name "unconnected-(U1A-PD1-Pad82)") (class "Default")
      (node (ref "U1") (pin "82") (pinfunction "PD1_82") (pintype "bidirectional"))
    )
    (net (code "83") (name "unconnected-(U1A-PD2-Pad83)") (class "Default")
      (node (ref "U1") (pin "83") (pinfunction "PD2_83") (pintype "bidirectional"))
    )
    (net (code "84") (name "unconnected-(U1A-PD3-Pad84)") (class "Default")
      (node (ref "U1") (pin "84") (pinfunction "PD3_84") (pintype "bidirectional"))
    )
    (net (code "85") (name "unconnected-(U1A-PD4-Pad85)") (class "Default")
      (node (ref "U1") (pin "85") (pinfunction "PD4_85") (pintype "bidirectional"))
    )
    (net (code "86") (name "unconnected-(U1A-PD5-Pad86)") (class "Default")
      (node (ref "U1") (pin "86") (pinfunction "PD5_86") (pintype "bidirectional"))
    )
    (net (code "87") (name "unconnected-(U1A-PD6-Pad87)") (class "Default")
      (node (ref "U1") (pin "87") (pinfunction "PD6_87") (pintype "bidirectional"))
    )
    (net (code "88") (name "unconnected-(U1A-PD7-Pad88)") (class "Default")
      (node (ref "U1") (pin "88") (pinfunction "PD7_88") (pintype "bidirectional"))
    )
    (net (code "89") (name "unconnected-(U1A-PD10-Pad57)") (class "Default")
      (node (ref "U1") (pin "57") (pinfunction "PD10_57") (pintype "bidirectional"))
    )
    (net (code "90") (name "unconnected-(U1A-PD11-Pad58)") (class "Default")
      (node (ref "U1") (pin "58") (pinfunction "PD11_58") (pintype "bidirectional"))
    )
    (net (code "91") (name "unconnected-(U1B-PE2-Pad1)") (class "Default")
      (node (ref "U1") (pin "1") (pinfunction "PE2_1") (pintype "bidirectional"))
    )
    (net (code "92") (name "unconnected-(U1B-PE3-Pad2)") (class "Default")
      (node (ref "U1") (pin "2") (pinfunction "PE3_2") (pintype "bidirectional"))
    )
    (net (code "93") (name "unconnected-(U1B-PE4-Pad3)") (class "Default")
      (node (ref "U1") (pin "3") (pinfunction "PE4_3") (pintype "bidirectional"))
    )
    (net (code "94") (name "unconnected-(U1B-PE5-Pad4)") (class "Default")
      (node (ref "U1") (pin "4") (pinfunction "PE5_4") (pintype "bidirectional"))
    )
    (net (code "95") (name "unconnected-(U1B-PE6-Pad5)") (class "Default")
      (node (ref "U1") (pin "5") (pinfunction "PE6_5") (pintype "bidirectional"))
    )
    (net (code "96") (name "unconnected-(U1B-PE7-Pad37)") (class "Default")
      (node (ref "U1") (pin "37") (pinfunction "PE7_37") (pintype "bidirectional"))
    )
    (net (code "97") (name "unconnected-(U1B-PE8-Pad38)") (class "Default")
      (node (ref "U1") (pin "38") (pinfunction "PE8_38") (pintype "bidirectional"))
    )
    (net (code "98") (name "unconnected-(U1B-PE9-Pad39)") (class "Default")
      (node (ref "U1") (pin "39") (pinfunction "PE9_39") (pintype "bidirectional"))
    )
    (net (code "99") (name "unconnected-(U1B-PE10-Pad40)") (class "Default")
      (node (ref "U1") (pin "40") (pinfunction "PE10_40") (pintype "bidirectional"))
    )
    (net (code "100") (name "unconnected-(U1B-PE12-Pad42)") (class "Default")
      (node (ref "U1") (pin "42") (pinfunction "PE12_42") (pintype "bidirectional"))
    )
    (net (code "101") (name "unconnected-(U1B-PE13-Pad43)") (class "Default")
      (node (ref "U1") (pin "43") (pinfunction "PE13_43") (pintype "bidirectional"))
    )
    (net (code "102") (name "unconnected-(U1B-PE15-Pad45)") (class "Default")
      (node (ref "U1") (pin "45") (pinfunction "PE15_45") (pintype "bidirectional"))
    )
    (net (code "103") (name "unconnected-(U1C-VREF+-Pad20)") (class "Default")
      (node (ref "U1") (pin "20") (pinfunction "VREF+_20") (pintype "power_in+no_connect"))
    )
    (net (code "104") (name "unconnected-(U2-A1-Pad13)") (class "Default")
      (node (ref "U2") (pin "13") (pinfunction "A1_13") (pintype "passive"))
    )
    (net (code "105") (name "unconnected-(U2-A2-Pad14)") (class "Default")
      (node (ref "U2") (pin "14") (pinfunction "A2_14") (pintype "passive"))
    )
    (net (code "106") (name "unconnected-(U2-B1-Pad12)") (class "Default")
      (node (ref "U2") (pin "12") (pinfunction "B1_12") (pintype "passive"))
    )
    (net (code "107") (name "unconnected-(U2-B2-Pad11)") (class "Default")
      (node (ref "U2") (pin "11") (pinfunction "B2_11") (pintype "passive"))
    )
    (net (code "108") (name "unconnected-(U2-ENABLE_M-Pad1)") (class "Default")
      (node (ref "U2") (pin "1") (pinfunction "ENABLE_M_1") (pintype "passive"))
    )
    (net (code "109") (name "unconnected-(U2-FAULT-Pad15)") (class "Default")
      (node (ref "U2") (pin "15") (pinfunction "FAULT_15") (pintype "passive"))
    )
    (net (code "110") (name "unconnected-(U2-VREF-Pad5)") (class "Default")
      (node (ref "U2") (pin "5") (pinfunction "VREF_5") (pintype "passive"))
    )
  )
)
